# 2025_07_18_bldc.net
KiCad netlist of a schematic drawn in EasyEDA Pro
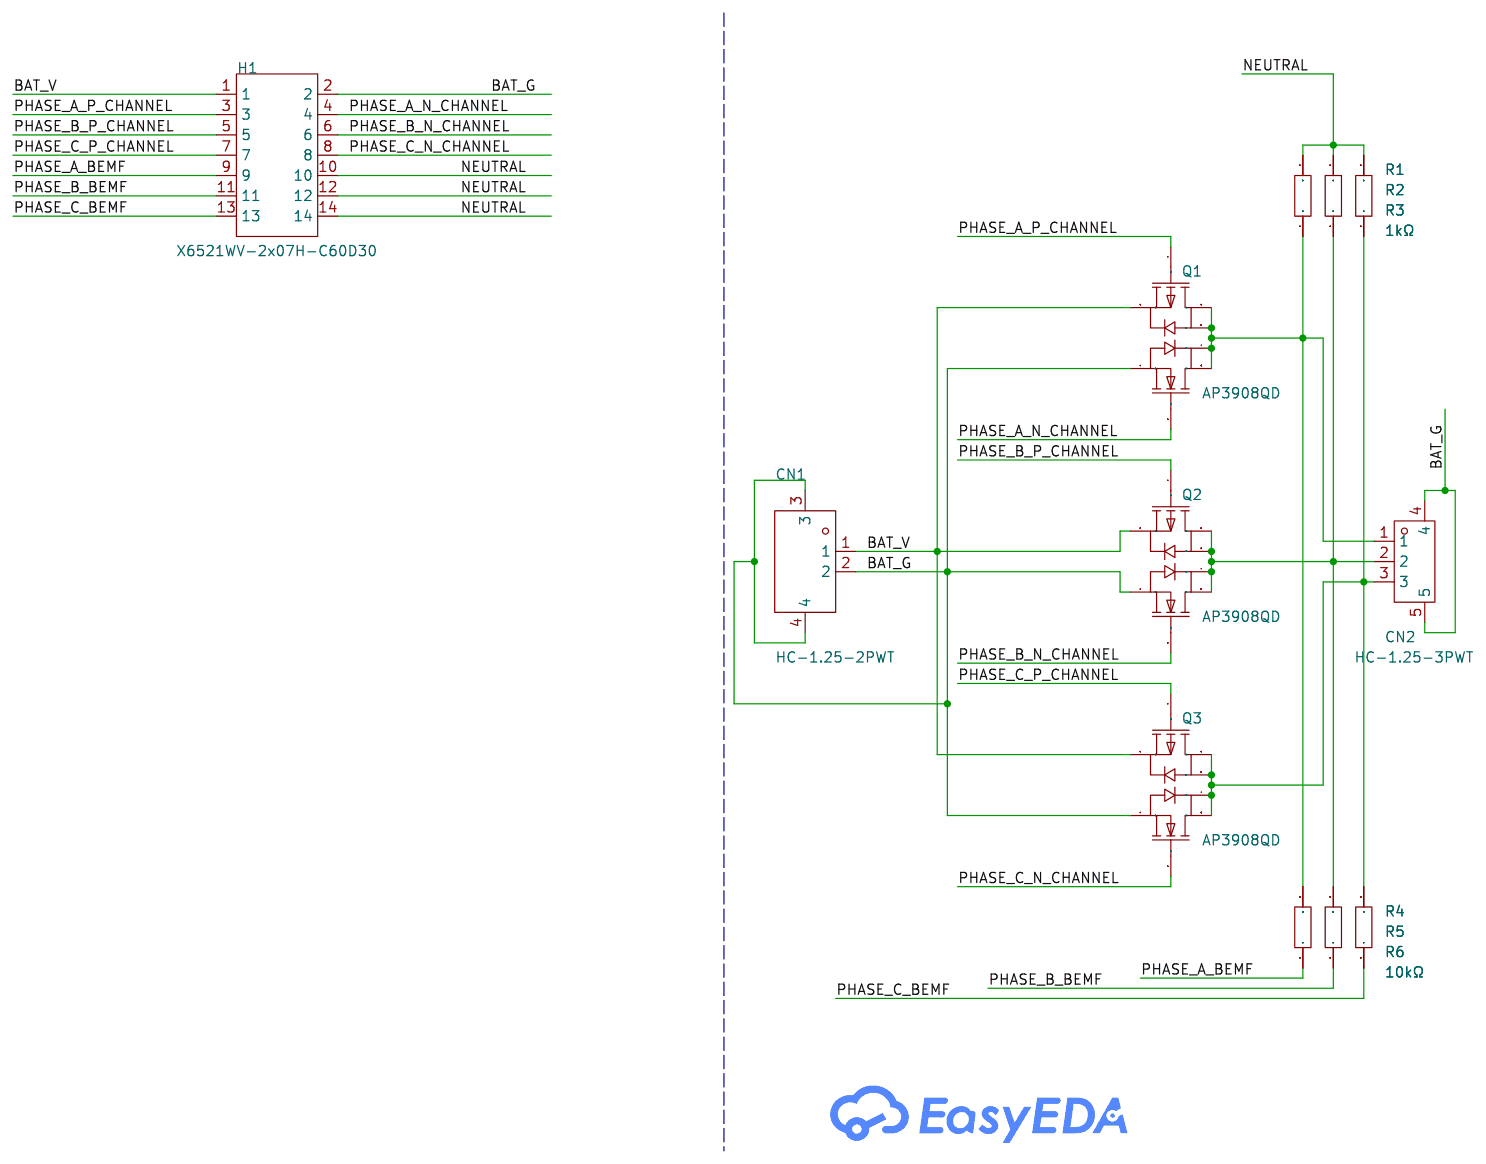
[diagram p0: schematic sheet]

(export (version "E")
  (design (tool "Eeschema 10.0.6"))
  (components
    (comp (ref "CN1")
      (value "HC-1.25-2PWT")
      (footprint "easyedapro:CONN-SMD_2P-P1.25-HC-1.25-2PWT")
      (fields (field (name "Manufacturer") "HCTL(华灿天禄)"))
      (libsource (lib "easyedapro") (part "HC-1.25-2PWT"))
    )
    (comp (ref "CN2")
      (value "HC-1.25-3PWT")
      (footprint "easyedapro:CONN-SMD_HC-1.25-3PWT")
      (fields (field (name "Manufacturer") "HCTL(华灿天禄)"))
      (libsource (lib "easyedapro") (part "HC-1.25-3PWT"))
    )
    (comp (ref "H1")
      (value "X6521WV-2x07H-C60D30")
      (footprint "easyedapro:HDR-TH_14P-P2.54-V-M-R2-C7-S2.54")
      (fields (field (name "Manufacturer") "XKB Connection(中国星坤)"))
      (libsource (lib "easyedapro") (part "X6521WV-2×07H-C30D60"))
    )
    (comp (ref "Q1")
      (value "AP3908QD")
      (footprint "easyedapro:DFN-8_L3.1-W3.2-P0.65-BL-EP")
      (fields (field (name "Manufacturer") "ALLPOWER(铨力)"))
      (libsource (lib "easyedapro") (part "AP3908QD"))
    )
    (comp (ref "Q2")
      (value "AP3908QD")
      (footprint "easyedapro:DFN-8_L3.1-W3.2-P0.65-BL-EP")
      (fields (field (name "Manufacturer") "ALLPOWER(铨力)"))
      (libsource (lib "easyedapro") (part "AP3908QD"))
    )
    (comp (ref "Q3")
      (value "AP3908QD")
      (footprint "easyedapro:DFN-8_L3.1-W3.2-P0.65-BL-EP")
      (fields (field (name "Manufacturer") "ALLPOWER(铨力)"))
      (libsource (lib "easyedapro") (part "AP3908QD"))
    )
    (comp (ref "R1")
      (value "1kΩ")
      (footprint "easyedapro:R0603")
      (fields
        (field (name "Manufacturer Part") "0603WAF1001T5E")
        (field (name "Manufacturer") "UNI-ROYAL(厚声)")
      )
      (libsource (lib "easyedapro") (part "0603WAF1001T5E"))
    )
    (comp (ref "R2")
      (value "1kΩ")
      (footprint "easyedapro:R0603")
      (fields
        (field (name "Manufacturer Part") "0603WAF1001T5E")
        (field (name "Manufacturer") "UNI-ROYAL(厚声)")
      )
      (libsource (lib "easyedapro") (part "0603WAF1001T5E"))
    )
    (comp (ref "R3")
      (value "1kΩ")
      (footprint "easyedapro:R0603")
      (fields
        (field (name "Manufacturer Part") "0603WAF1001T5E")
        (field (name "Manufacturer") "UNI-ROYAL(厚声)")
      )
      (libsource (lib "easyedapro") (part "0603WAF1001T5E"))
    )
    (comp (ref "R4")
      (value "10kΩ")
      (footprint "easyedapro:R0603")
      (fields (field (name "Manufacturer Part") "RC0603FR-0710KL") (field (name "Manufacturer") "YAGEO(国巨)"))
      (libsource (lib "easyedapro") (part "RC0603FR-0710KL"))
    )
    (comp (ref "R5")
      (value "10kΩ")
      (footprint "easyedapro:R0603")
      (fields (field (name "Manufacturer Part") "RC0603FR-0710KL") (field (name "Manufacturer") "YAGEO(国巨)"))
      (libsource (lib "easyedapro") (part "RC0603FR-0710KL"))
    )
    (comp (ref "R6")
      (value "10kΩ")
      (footprint "easyedapro:R0603")
      (fields (field (name "Manufacturer Part") "RC0603FR-0710KL") (field (name "Manufacturer") "YAGEO(国巨)"))
      (libsource (lib "easyedapro") (part "RC0603FR-0710KL"))
    )
  )
  (nets
    (net (code "1") (name "/BAT_G") (class "Default")
      (node (ref "CN1") (pin "2") (pinfunction "2_2") (pintype "unspecified"))
      (node (ref "CN1") (pin "3") (pinfunction "3_3") (pintype "unspecified"))
      (node (ref "CN1") (pin "4") (pinfunction "4_4") (pintype "unspecified"))
      (node (ref "CN2") (pin "4") (pinfunction "4_4") (pintype "unspecified"))
      (node (ref "CN2") (pin "5") (pinfunction "5_5") (pintype "unspecified"))
      (node (ref "H1") (pin "2") (pinfunction "2_2") (pintype "unspecified"))
      (node (ref "Q1") (pin "1") (pinfunction "S_1") (pintype "unspecified"))
      (node (ref "Q2") (pin "1") (pinfunction "S_1") (pintype "unspecified"))
      (node (ref "Q3") (pin "1") (pinfunction "S_1") (pintype "unspecified"))
    )
    (net (code "2") (name "/BAT_V") (class "Default")
      (node (ref "CN1") (pin "1") (pinfunction "1_1") (pintype "unspecified"))
      (node (ref "H1") (pin "1") (pinfunction "1_1") (pintype "unspecified"))
      (node (ref "Q1") (pin "3") (pinfunction "S_3") (pintype "unspecified"))
      (node (ref "Q2") (pin "3") (pinfunction "S_3") (pintype "unspecified"))
      (node (ref "Q3") (pin "3") (pinfunction "S_3") (pintype "unspecified"))
    )
    (net (code "3") (name "/NEUTRAL") (class "Default")
      (node (ref "H1") (pin "10") (pinfunction "10_10") (pintype "unspecified"))
      (node (ref "H1") (pin "12") (pinfunction "12_12") (pintype "unspecified"))
      (node (ref "H1") (pin "14") (pinfunction "14_14") (pintype "unspecified"))
      (node (ref "R1") (pin "2") (pinfunction "2_2") (pintype "input"))
      (node (ref "R2") (pin "2") (pinfunction "2_2") (pintype "input"))
      (node (ref "R3") (pin "2") (pinfunction "2_2") (pintype "input"))
    )
    (net (code "4") (name "/PHASE_A_BEMF") (class "Default")
      (node (ref "H1") (pin "9") (pinfunction "9_9") (pintype "unspecified"))
      (node (ref "R4") (pin "1") (pinfunction "1_1") (pintype "input"))
    )
    (net (code "5") (name "/PHASE_A_N_CHANNEL") (class "Default")
      (node (ref "H1") (pin "4") (pinfunction "4_4") (pintype "unspecified"))
      (node (ref "Q1") (pin "2") (pinfunction "G_2") (pintype "unspecified"))
    )
    (net (code "6") (name "/PHASE_A_P_CHANNEL") (class "Default")
      (node (ref "H1") (pin "3") (pinfunction "3_3") (pintype "unspecified"))
      (node (ref "Q1") (pin "4") (pinfunction "G_4") (pintype "unspecified"))
    )
    (net (code "7") (name "/PHASE_B_BEMF") (class "Default")
      (node (ref "H1") (pin "11") (pinfunction "11_11") (pintype "unspecified"))
      (node (ref "R5") (pin "1") (pinfunction "1_1") (pintype "input"))
    )
    (net (code "8") (name "/PHASE_B_N_CHANNEL") (class "Default")
      (node (ref "H1") (pin "6") (pinfunction "6_6") (pintype "unspecified"))
      (node (ref "Q2") (pin "2") (pinfunction "G_2") (pintype "unspecified"))
    )
    (net (code "9") (name "/PHASE_B_P_CHANNEL") (class "Default")
      (node (ref "H1") (pin "5") (pinfunction "5_5") (pintype "unspecified"))
      (node (ref "Q2") (pin "4") (pinfunction "G_4") (pintype "unspecified"))
    )
    (net (code "10") (name "/PHASE_C_BEMF") (class "Default")
      (node (ref "H1") (pin "13") (pinfunction "13_13") (pintype "unspecified"))
      (node (ref "R6") (pin "1") (pinfunction "1_1") (pintype "input"))
    )
    (net (code "11") (name "/PHASE_C_N_CHANNEL") (class "Default")
      (node (ref "H1") (pin "8") (pinfunction "8_8") (pintype "unspecified"))
      (node (ref "Q3") (pin "2") (pinfunction "G_2") (pintype "unspecified"))
    )
    (net (code "12") (name "/PHASE_C_P_CHANNEL") (class "Default")
      (node (ref "H1") (pin "7") (pinfunction "7_7") (pintype "unspecified"))
      (node (ref "Q3") (pin "4") (pinfunction "G_4") (pintype "unspecified"))
    )
    (net (code "13") (name "Net-(CN2-Pad1)") (class "Default")
      (node (ref "CN2") (pin "1") (pinfunction "1_1") (pintype "unspecified"))
      (node (ref "Q1") (pin "5") (pinfunction "D_5") (pintype "unspecified"))
      (node (ref "Q1") (pin "6") (pinfunction "D_6") (pintype "unspecified"))
      (node (ref "Q1") (pin "7") (pinfunction "D_7") (pintype "unspecified"))
      (node (ref "Q1") (pin "8") (pinfunction "D_8") (pintype "unspecified"))
      (node (ref "R1") (pin "1") (pinfunction "1_1") (pintype "input"))
      (node (ref "R4") (pin "2") (pinfunction "2_2") (pintype "input"))
    )
    (net (code "14") (name "Net-(CN2-Pad2)") (class "Default")
      (node (ref "CN2") (pin "2") (pinfunction "2_2") (pintype "unspecified"))
      (node (ref "Q2") (pin "5") (pinfunction "D_5") (pintype "unspecified"))
      (node (ref "Q2") (pin "6") (pinfunction "D_6") (pintype "unspecified"))
      (node (ref "Q2") (pin "7") (pinfunction "D_7") (pintype "unspecified"))
      (node (ref "Q2") (pin "8") (pinfunction "D_8") (pintype "unspecified"))
      (node (ref "R2") (pin "1") (pinfunction "1_1") (pintype "input"))
      (node (ref "R5") (pin "2") (pinfunction "2_2") (pintype "input"))
    )
    (net (code "15") (name "Net-(CN2-Pad3)") (class "Default")
      (node (ref "CN2") (pin "3") (pinfunction "3_3") (pintype "unspecified"))
      (node (ref "Q3") (pin "5") (pinfunction "D_5") (pintype "unspecified"))
      (node (ref "Q3") (pin "6") (pinfunction "D_6") (pintype "unspecified"))
      (node (ref "Q3") (pin "7") (pinfunction "D_7") (pintype "unspecified"))
      (node (ref "Q3") (pin "8") (pinfunction "D_8") (pintype "unspecified"))
      (node (ref "R3") (pin "1") (pinfunction "1_1") (pintype "input"))
      (node (ref "R6") (pin "2") (pinfunction "2_2") (pintype "input"))
    )
  )
)
